# MSP430F149.net
KiCad netlist of a schematic drawn in Altium Designer
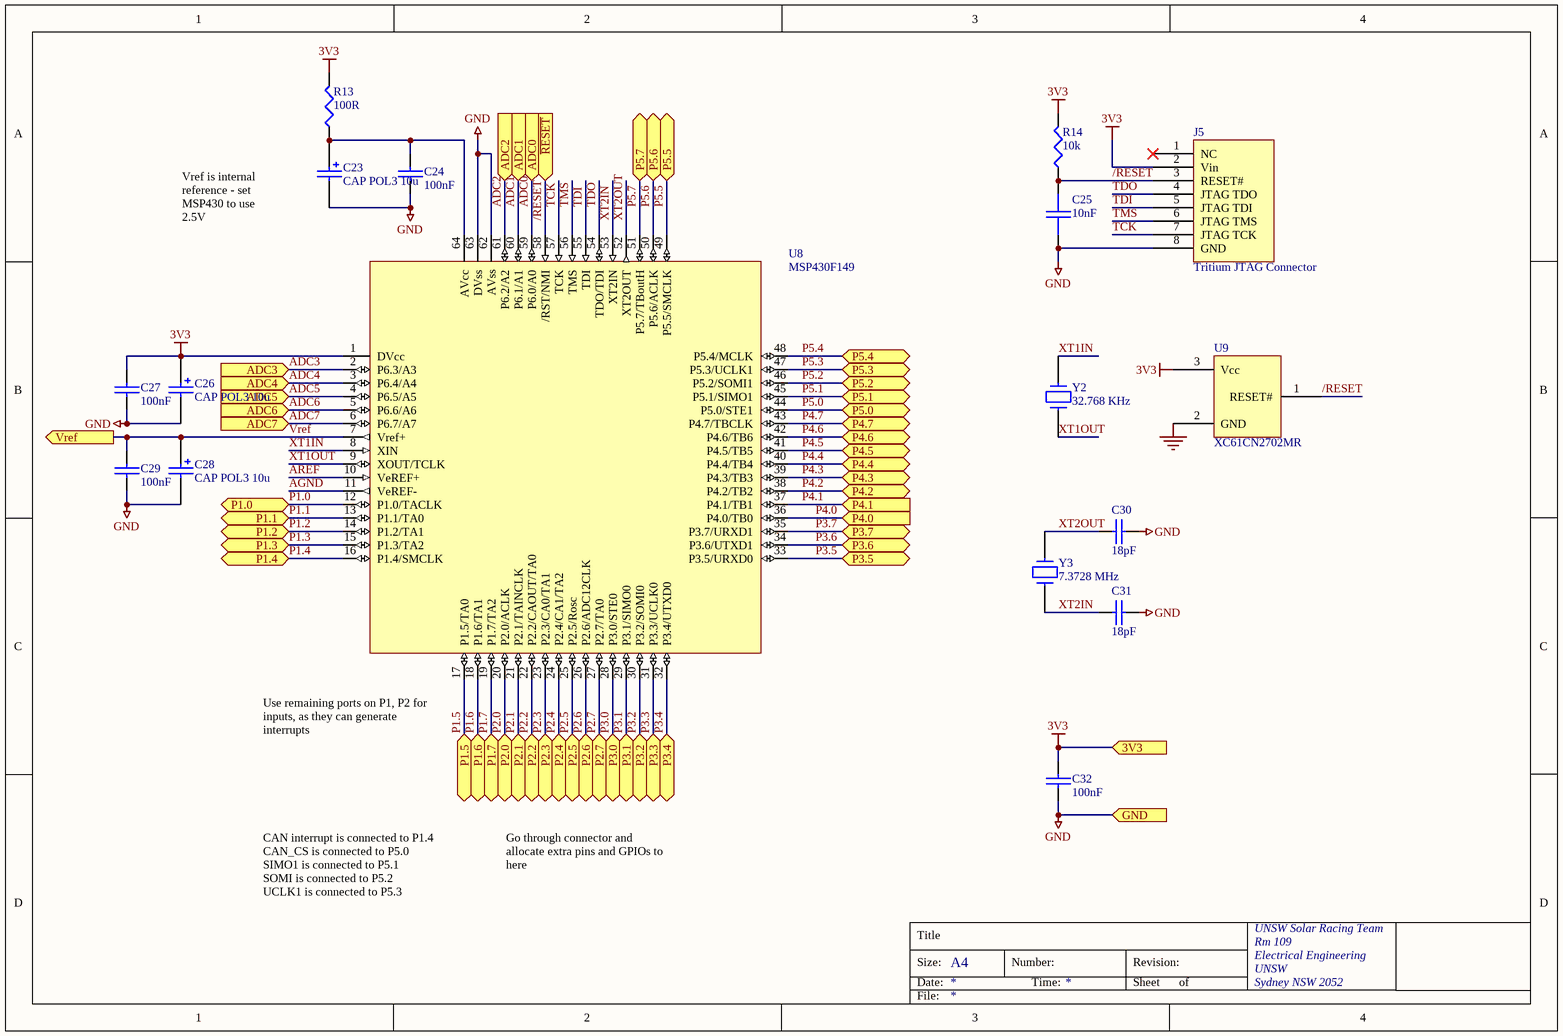
[diagram p0: MSP430F149.SCHDOC]

(export (version "E")
  (design (tool "Eeschema 10.0.6"))
  (components
    (comp (ref "C23")
      (value "CAP POL3 10u")
      (footprint "MCCT-CASEA")
      (description "Polarized Capacitor (Surface Mount)")
      (libsource (lib "RCLDQ") (part "CAP POL3"))
    )
    (comp (ref "C24")
      (value "100nF")
      (footprint "0603")
      (description "Capacitor")
      (libsource (lib "*") (part "CAP"))
    )
    (comp (ref "C25")
      (value "10nF")
      (footprint "0603")
      (description "Capacitor")
      (libsource (lib "SunswiftLib20030312RR") (part "CAP"))
    )
    (comp (ref "C26")
      (value "CAP POL3 10u")
      (footprint "MCCT-CASEA")
      (description "Polarized Capacitor (Surface Mount)")
      (libsource (lib "RCLDQ") (part "CAP POL3"))
    )
    (comp (ref "C27")
      (value "100nF")
      (footprint "0603")
      (description "Capacitor")
      (libsource (lib "*") (part "CAP"))
    )
    (comp (ref "C28")
      (value "CAP POL3 10u")
      (footprint "MCCT-CASEA")
      (description "Polarized Capacitor (Surface Mount)")
      (libsource (lib "RCLDQ") (part "CAP POL3"))
    )
    (comp (ref "C29")
      (value "100nF")
      (footprint "0603")
      (description "Capacitor")
      (libsource (lib "*") (part "CAP"))
    )
    (comp (ref "C30")
      (value "18pF")
      (footprint "0603")
      (description "Capacitor")
      (libsource (lib "*") (part "CAP"))
    )
    (comp (ref "C31")
      (value "18pF")
      (footprint "0603")
      (description "Capacitor")
      (libsource (lib "*") (part "CAP"))
    )
    (comp (ref "C32")
      (value "100nF")
      (footprint "0603")
      (description "Capacitor")
      (libsource (lib "*") (part "CAP"))
    )
    (comp (ref "J5")
      (value "Tritium JTAG Connector")
      (footprint "HDR2X5")
      (description "Tritium JTAG interface for MSP430")
      (libsource (lib "SunswiftLib20030312RR") (part "430F_JTAG_TRITIUM"))
    )
    (comp (ref "R13")
      (value "100R")
      (footprint "0603")
      (description "Resistor")
      (libsource (lib "SunswiftLib20030312RR") (part "RES1"))
    )
    (comp (ref "R14")
      (value "10k")
      (footprint "0603")
      (description "Resistor")
      (libsource (lib "SunswiftLib20030312RR") (part "RES1"))
    )
    (comp (ref "U8")
      (value "MSP430F149")
      (footprint "QFP64")
      (libsource (lib "SunswiftLib20030312RR") (part "MSP430F14X"))
    )
    (comp (ref "U9")
      (value "XC61CN2702MR")
      (footprint "SOT23-3")
      (description "SOT23 reset generator")
      (libsource (lib "*") (part "XC61F"))
    )
    (comp (ref "Y2")
      (value "32.768 KHz")
      (footprint "WATCHA")
      (description "Crystal")
      (libsource (lib "*") (part "CRYSTAL"))
    )
    (comp (ref "Y3")
      (value "7.3728 MHz")
      (footprint "HC49/4H")
      (description "Crystal")
      (libsource (lib "*") (part "CRYSTAL"))
    )
  )
  (nets
    (net (code "1") (name "/ADC0") (class "Default")
      (node (ref "U8") (pin "59") (pinfunction "P6.0/A0_59") (pintype "bidirectional"))
    )
    (net (code "2") (name "/ADC1") (class "Default")
      (node (ref "U8") (pin "60") (pinfunction "P6.1/A1_60") (pintype "bidirectional"))
    )
    (net (code "3") (name "/ADC2") (class "Default")
      (node (ref "U8") (pin "61") (pinfunction "P6.2/A2_61") (pintype "bidirectional"))
    )
    (net (code "4") (name "/ADC3") (class "Default")
      (node (ref "U8") (pin "2") (pinfunction "P6.3/A3_2") (pintype "bidirectional"))
    )
    (net (code "5") (name "/ADC4") (class "Default")
      (node (ref "U8") (pin "3") (pinfunction "P6.4/A4_3") (pintype "bidirectional"))
    )
    (net (code "6") (name "/ADC5") (class "Default")
      (node (ref "U8") (pin "4") (pinfunction "P6.5/A5_4") (pintype "bidirectional"))
    )
    (net (code "7") (name "/ADC6") (class "Default")
      (node (ref "U8") (pin "5") (pinfunction "P6.6/A6_5") (pintype "bidirectional"))
    )
    (net (code "8") (name "/ADC7") (class "Default")
      (node (ref "U8") (pin "6") (pinfunction "P6.7/A7_6") (pintype "bidirectional"))
    )
    (net (code "9") (name "/AGND") (class "Default")
      (node (ref "U8") (pin "11") (pinfunction "VeREF-_11") (pintype "output"))
    )
    (net (code "10") (name "/AREF") (class "Default")
      (node (ref "U8") (pin "10") (pinfunction "VeREF+_10") (pintype "input"))
    )
    (net (code "11") (name "/P1.0") (class "Default")
      (node (ref "U8") (pin "12") (pinfunction "P1.0/TACLK_12") (pintype "bidirectional"))
    )
    (net (code "12") (name "/P1.1") (class "Default")
      (node (ref "U8") (pin "13") (pinfunction "P1.1/TA0_13") (pintype "bidirectional"))
    )
    (net (code "13") (name "/P1.2") (class "Default")
      (node (ref "U8") (pin "14") (pinfunction "P1.2/TA1_14") (pintype "bidirectional"))
    )
    (net (code "14") (name "/P1.3") (class "Default")
      (node (ref "U8") (pin "15") (pinfunction "P1.3/TA2_15") (pintype "bidirectional"))
    )
    (net (code "15") (name "/P1.4") (class "Default")
      (node (ref "U8") (pin "16") (pinfunction "P1.4/SMCLK_16") (pintype "bidirectional"))
    )
    (net (code "16") (name "/P1.5") (class "Default")
      (node (ref "U8") (pin "17") (pinfunction "P1.5/TA0_17") (pintype "bidirectional"))
    )
    (net (code "17") (name "/P1.6") (class "Default")
      (node (ref "U8") (pin "18") (pinfunction "P1.6/TA1_18") (pintype "bidirectional"))
    )
    (net (code "18") (name "/P1.7") (class "Default")
      (node (ref "U8") (pin "19") (pinfunction "P1.7/TA2_19") (pintype "bidirectional"))
    )
    (net (code "19") (name "/P2.0") (class "Default")
      (node (ref "U8") (pin "20") (pinfunction "P2.0/ACLK_20") (pintype "bidirectional"))
    )
    (net (code "20") (name "/P2.1") (class "Default")
      (node (ref "U8") (pin "21") (pinfunction "P2.1/TAINCLK_21") (pintype "bidirectional"))
    )
    (net (code "21") (name "/P2.2") (class "Default")
      (node (ref "U8") (pin "22") (pinfunction "P2.2/CAOUT/TA0_22") (pintype "bidirectional"))
    )
    (net (code "22") (name "/P2.3") (class "Default")
      (node (ref "U8") (pin "23") (pinfunction "P2.3/CA0/TA1_23") (pintype "bidirectional"))
    )
    (net (code "23") (name "/P2.4") (class "Default")
      (node (ref "U8") (pin "24") (pinfunction "P2.4/CA1/TA2_24") (pintype "bidirectional"))
    )
    (net (code "24") (name "/P2.5") (class "Default")
      (node (ref "U8") (pin "25") (pinfunction "P2.5/Rosc_25") (pintype "bidirectional"))
    )
    (net (code "25") (name "/P2.6") (class "Default")
      (node (ref "U8") (pin "26") (pinfunction "P2.6/ADC12CLK_26") (pintype "bidirectional"))
    )
    (net (code "26") (name "/P2.7") (class "Default")
      (node (ref "U8") (pin "27") (pinfunction "P2.7/TA0_27") (pintype "bidirectional"))
    )
    (net (code "27") (name "/P3.0") (class "Default")
      (node (ref "U8") (pin "28") (pinfunction "P3.0/STE0_28") (pintype "bidirectional"))
    )
    (net (code "28") (name "/P3.1") (class "Default")
      (node (ref "U8") (pin "29") (pinfunction "P3.1/SIMO0_29") (pintype "bidirectional"))
    )
    (net (code "29") (name "/P3.2") (class "Default")
      (node (ref "U8") (pin "30") (pinfunction "P3.2/SOMI0_30") (pintype "bidirectional"))
    )
    (net (code "30") (name "/P3.3") (class "Default")
      (node (ref "U8") (pin "31") (pinfunction "P3.3/UCLK0_31") (pintype "bidirectional"))
    )
    (net (code "31") (name "/P3.4") (class "Default")
      (node (ref "U8") (pin "32") (pinfunction "P3.4/UTXD0_32") (pintype "bidirectional"))
    )
    (net (code "32") (name "/P3.5") (class "Default")
      (node (ref "U8") (pin "33") (pinfunction "P3.5/URXD0_33") (pintype "bidirectional"))
    )
    (net (code "33") (name "/P3.6") (class "Default")
      (node (ref "U8") (pin "34") (pinfunction "P3.6/UTXD1_34") (pintype "bidirectional"))
    )
    (net (code "34") (name "/P3.7") (class "Default")
      (node (ref "U8") (pin "35") (pinfunction "P3.7/URXD1_35") (pintype "bidirectional"))
    )
    (net (code "35") (name "/P4.0") (class "Default")
      (node (ref "U8") (pin "36") (pinfunction "P4.0/TB0_36") (pintype "bidirectional"))
    )
    (net (code "36") (name "/P4.1") (class "Default")
      (node (ref "U8") (pin "37") (pinfunction "P4.1/TB1_37") (pintype "bidirectional"))
    )
    (net (code "37") (name "/P4.2") (class "Default")
      (node (ref "U8") (pin "38") (pinfunction "P4.2/TB2_38") (pintype "bidirectional"))
    )
    (net (code "38") (name "/P4.3") (class "Default")
      (node (ref "U8") (pin "39") (pinfunction "P4.3/TB3_39") (pintype "bidirectional"))
    )
    (net (code "39") (name "/P4.4") (class "Default")
      (node (ref "U8") (pin "40") (pinfunction "P4.4/TB4_40") (pintype "bidirectional"))
    )
    (net (code "40") (name "/P4.5") (class "Default")
      (node (ref "U8") (pin "41") (pinfunction "P4.5/TB5_41") (pintype "bidirectional"))
    )
    (net (code "41") (name "/P4.6") (class "Default")
      (node (ref "U8") (pin "42") (pinfunction "P4.6/TB6_42") (pintype "bidirectional"))
    )
    (net (code "42") (name "/P4.7") (class "Default")
      (node (ref "U8") (pin "43") (pinfunction "P4.7/TBCLK_43") (pintype "bidirectional"))
    )
    (net (code "43") (name "/P5.0") (class "Default")
      (node (ref "U8") (pin "44") (pinfunction "P5.0/STE1_44") (pintype "bidirectional"))
    )
    (net (code "44") (name "/P5.1") (class "Default")
      (node (ref "U8") (pin "45") (pinfunction "P5.1/SIMO1_45") (pintype "bidirectional"))
    )
    (net (code "45") (name "/P5.2") (class "Default")
      (node (ref "U8") (pin "46") (pinfunction "P5.2/SOMI1_46") (pintype "bidirectional"))
    )
    (net (code "46") (name "/P5.3") (class "Default")
      (node (ref "U8") (pin "47") (pinfunction "P5.3/UCLK1_47") (pintype "bidirectional"))
    )
    (net (code "47") (name "/P5.4") (class "Default")
      (node (ref "U8") (pin "48") (pinfunction "P5.4/MCLK_48") (pintype "bidirectional"))
    )
    (net (code "48") (name "/P5.5") (class "Default")
      (node (ref "U8") (pin "49") (pinfunction "P5.5/SMCLK_49") (pintype "bidirectional"))
    )
    (net (code "49") (name "/P5.6") (class "Default")
      (node (ref "U8") (pin "50") (pinfunction "P5.6/ACLK_50") (pintype "bidirectional"))
    )
    (net (code "50") (name "/P5.7") (class "Default")
      (node (ref "U8") (pin "51") (pinfunction "P5.7/TBoutH_51") (pintype "bidirectional"))
    )
    (net (code "51") (name "/TCK") (class "Default")
      (node (ref "J5") (pin "7") (pinfunction "JTAG_TCK_7") (pintype "passive"))
      (node (ref "U8") (pin "57") (pinfunction "TCK_57") (pintype "input"))
    )
    (net (code "52") (name "/TDI") (class "Default")
      (node (ref "J5") (pin "5") (pinfunction "JTAG_TDI_5") (pintype "passive"))
      (node (ref "U8") (pin "55") (pinfunction "TDI_55") (pintype "input"))
    )
    (net (code "53") (name "/TDO") (class "Default")
      (node (ref "J5") (pin "4") (pinfunction "JTAG_TDO_4") (pintype "passive"))
      (node (ref "U8") (pin "54") (pinfunction "TDO/TDI_54") (pintype "bidirectional"))
    )
    (net (code "54") (name "/TMS") (class "Default")
      (node (ref "J5") (pin "6") (pinfunction "JTAG_TMS_6") (pintype "passive"))
      (node (ref "U8") (pin "56") (pinfunction "TMS_56") (pintype "input"))
    )
    (net (code "55") (name "/Vref") (class "Default")
      (node (ref "C28") (pin "1") (pinfunction "1_1") (pintype "passive"))
      (node (ref "C29") (pin "1") (pinfunction "1_1") (pintype "passive"))
      (node (ref "U8") (pin "7") (pinfunction "Vref+_7") (pintype "output"))
    )
    (net (code "56") (name "/XT1IN") (class "Default")
      (node (ref "U8") (pin "8") (pinfunction "XIN_8") (pintype "input"))
      (node (ref "Y2") (pin "2") (pinfunction "2_2") (pintype "passive"))
    )
    (net (code "57") (name "/XT1OUT") (class "Default")
      (node (ref "U8") (pin "9") (pinfunction "XOUT/TCLK_9") (pintype "bidirectional"))
      (node (ref "Y2") (pin "1") (pinfunction "1_1") (pintype "passive"))
    )
    (net (code "58") (name "/XT2IN") (class "Default")
      (node (ref "C31") (pin "1") (pinfunction "1_1") (pintype "passive"))
      (node (ref "U8") (pin "53") (pinfunction "XT2IN_53") (pintype "input"))
      (node (ref "Y3") (pin "1") (pinfunction "1_1") (pintype "passive"))
    )
    (net (code "59") (name "/XT2OUT") (class "Default")
      (node (ref "C30") (pin "1") (pinfunction "1_1") (pintype "passive"))
      (node (ref "U8") (pin "52") (pinfunction "XT2OUT_52") (pintype "output"))
      (node (ref "Y3") (pin "2") (pinfunction "2_2") (pintype "passive"))
    )
    (net (code "60") (name "/{slash}RESET") (class "Default")
      (node (ref "C25") (pin "1") (pinfunction "1_1") (pintype "passive"))
      (node (ref "J5") (pin "3") (pinfunction "RESET#_3") (pintype "passive"))
      (node (ref "R14") (pin "1") (pinfunction "1_1") (pintype "passive"))
      (node (ref "U8") (pin "58") (pinfunction "/RST/NMI_58") (pintype "input"))
      (node (ref "U9") (pin "1") (pinfunction "RESET#_1") (pintype "passive"))
    )
    (net (code "61") (name "3V3") (class "Default")
      (node (ref "C26") (pin "1") (pinfunction "1_1") (pintype "passive"))
      (node (ref "C27") (pin "1") (pinfunction "1_1") (pintype "passive"))
      (node (ref "C32") (pin "1") (pinfunction "1_1") (pintype "passive"))
      (node (ref "J5") (pin "2") (pinfunction "Vin_2") (pintype "passive"))
      (node (ref "R13") (pin "2") (pinfunction "2_2") (pintype "passive"))
      (node (ref "R14") (pin "2") (pinfunction "2_2") (pintype "passive"))
      (node (ref "U8") (pin "1") (pinfunction "DVcc_1") (pintype "power_in"))
      (node (ref "U9") (pin "3") (pinfunction "Vcc_3") (pintype "passive"))
    )
    (net (code "62") (name "GND") (class "Default")
      (node (ref "C23") (pin "2") (pinfunction "2_2") (pintype "passive"))
      (node (ref "C24") (pin "2") (pinfunction "2_2") (pintype "passive"))
      (node (ref "C25") (pin "2") (pinfunction "2_2") (pintype "passive"))
      (node (ref "C26") (pin "2") (pinfunction "2_2") (pintype "passive"))
      (node (ref "C27") (pin "2") (pinfunction "2_2") (pintype "passive"))
      (node (ref "C28") (pin "2") (pinfunction "2_2") (pintype "passive"))
      (node (ref "C29") (pin "2") (pinfunction "2_2") (pintype "passive"))
      (node (ref "C30") (pin "2") (pinfunction "2_2") (pintype "passive"))
      (node (ref "C31") (pin "2") (pinfunction "2_2") (pintype "passive"))
      (node (ref "C32") (pin "2") (pinfunction "2_2") (pintype "passive"))
      (node (ref "J5") (pin "8") (pinfunction "GND_8") (pintype "passive"))
      (node (ref "U8") (pin "62") (pinfunction "AVss_62") (pintype "power_in"))
      (node (ref "U8") (pin "63") (pinfunction "DVss_63") (pintype "power_in"))
      (node (ref "U9") (pin "2") (pinfunction "GND_2") (pintype "passive"))
    )
    (net (code "63") (name "Net-(U8-AVcc)") (class "Default")
      (node (ref "C23") (pin "1") (pinfunction "1_1") (pintype "passive"))
      (node (ref "C24") (pin "1") (pinfunction "1_1") (pintype "passive"))
      (node (ref "R13") (pin "1") (pinfunction "1_1") (pintype "passive"))
      (node (ref "U8") (pin "64") (pinfunction "AVcc_64") (pintype "power_in"))
    )
    (net (code "64") (name "unconnected-(J5-NC-Pad1)") (class "Default")
      (node (ref "J5") (pin "1") (pinfunction "NC_1") (pintype "passive+no_connect"))
    )
  )
)
